# clever_watch.net
KiCad netlist of a schematic drawn in Altium Designer
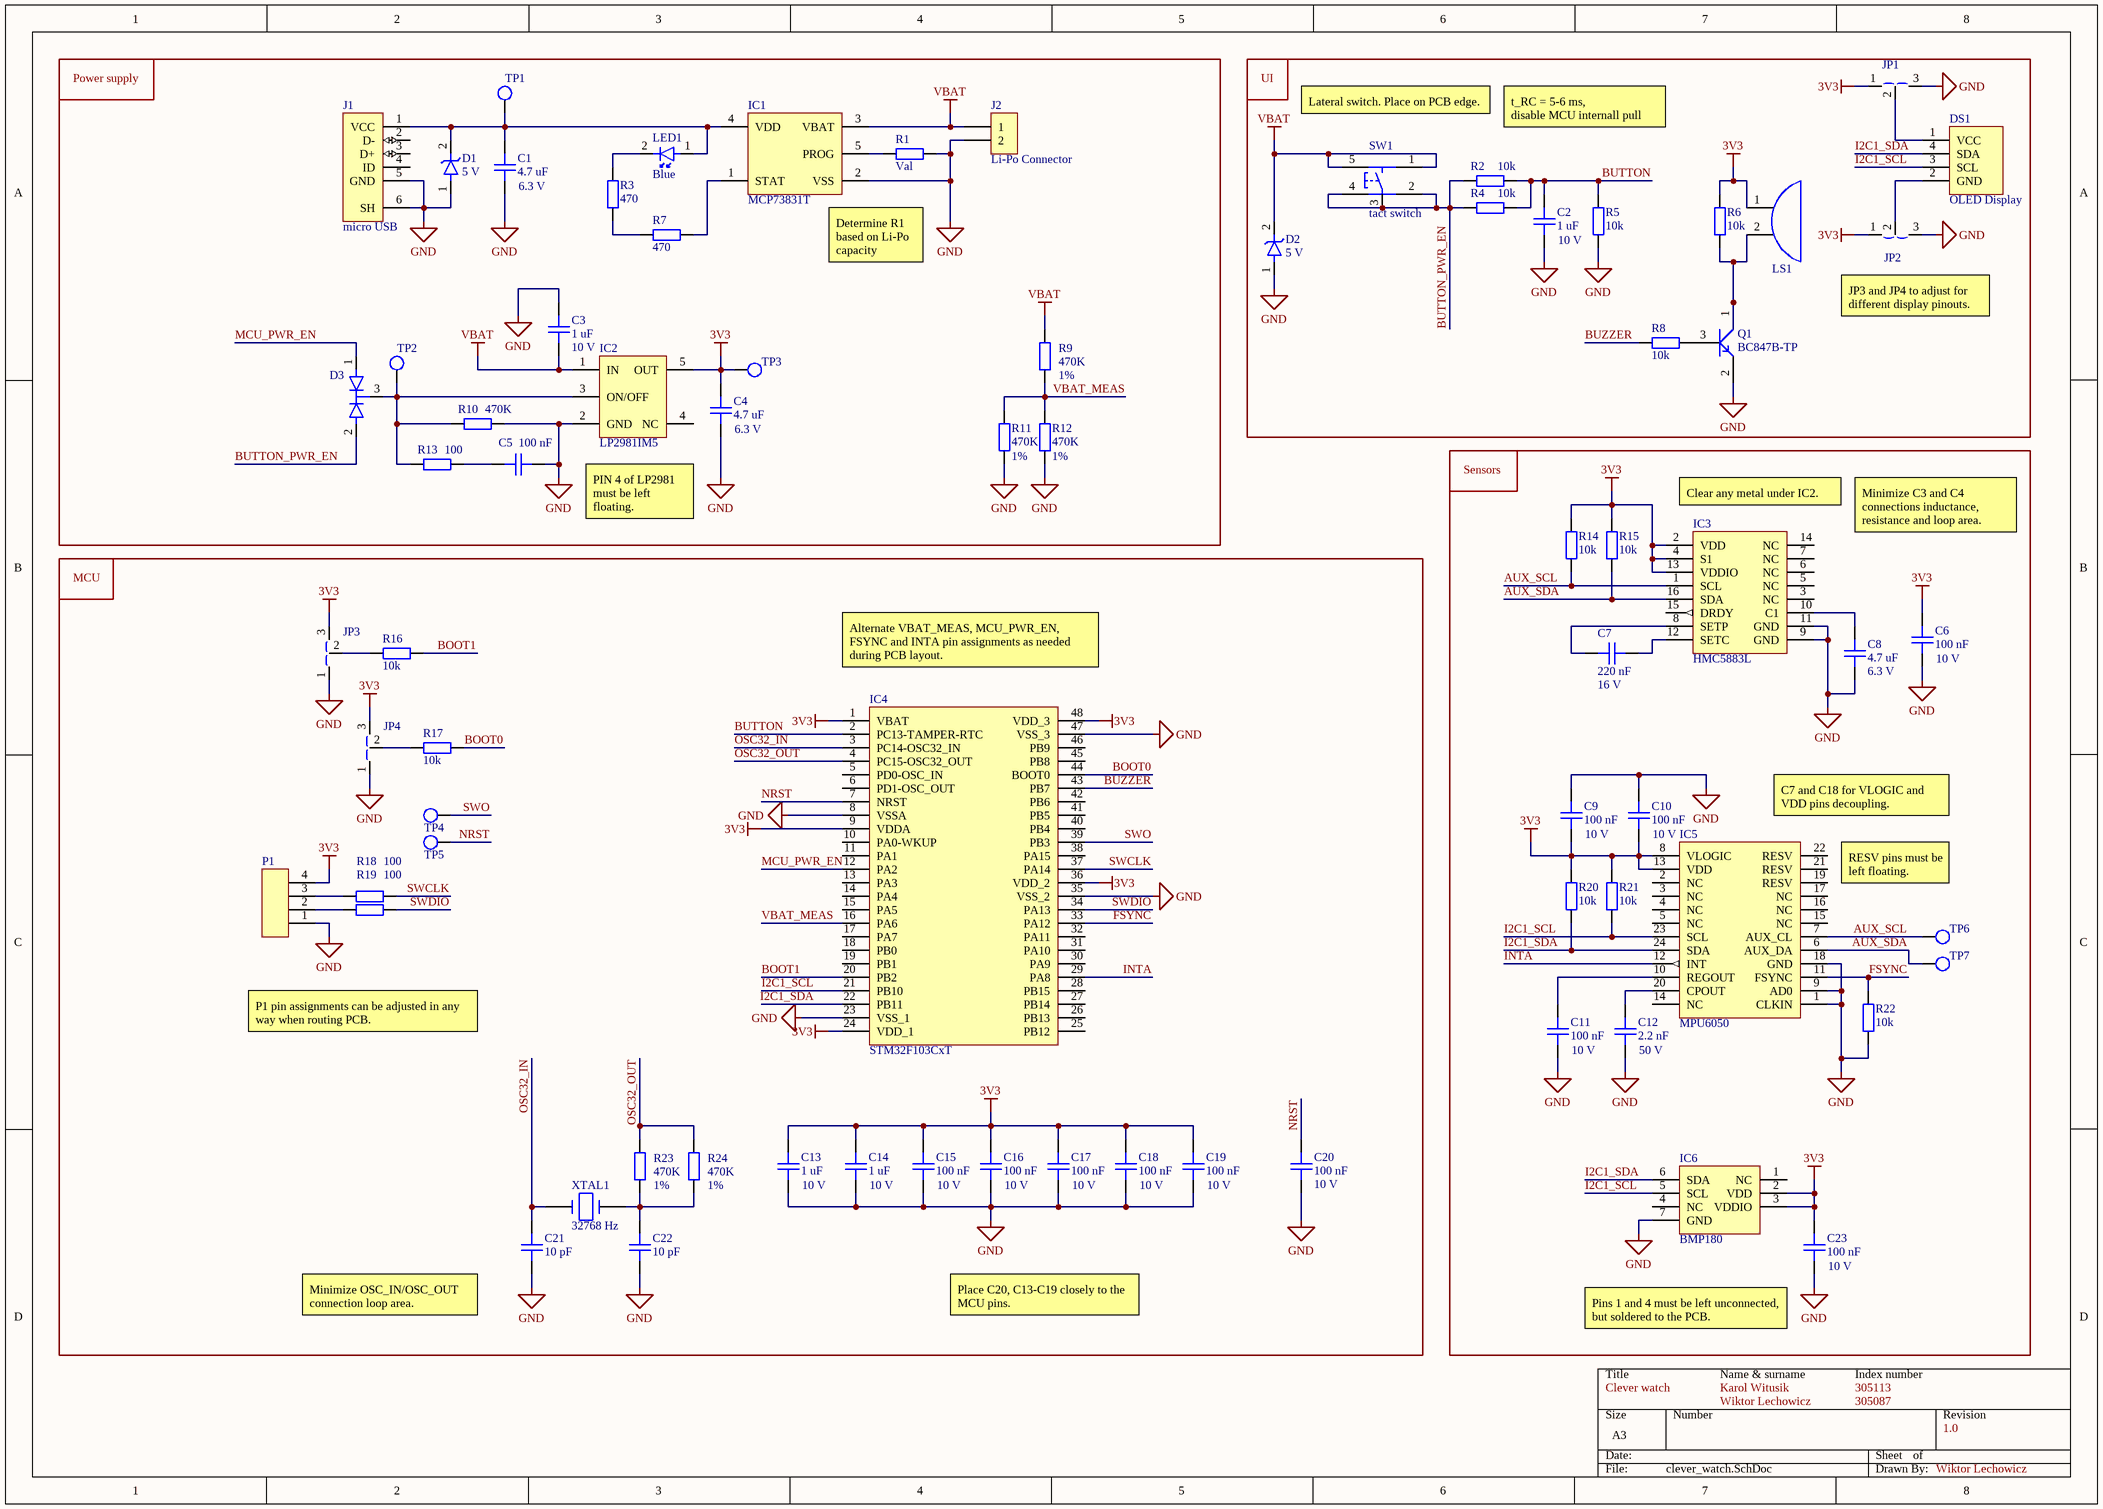
[diagram p0: clever_watch.SchDoc]

(export (version "E")
  (design (tool "Eeschema 10.0.6"))
  (components
    (comp (ref "C1")
      (value "4.7 uF")
      (footprint "C0402")
      (fields (field (name "MPN") "GRM155R60J475ME87D") (field (name "RATED VOLTAGE") "6.3 V"))
      (libsource (lib "clever_watch") (part "C"))
    )
    (comp (ref "C2")
      (value "1 uF")
      (footprint "C0402")
      (fields (field (name "MPN") "GRM155R61A105KE15J") (field (name "RATED VOLTAGE") "10 V"))
      (libsource (lib "clever_watch") (part "C"))
    )
    (comp (ref "C3")
      (value "1 uF")
      (footprint "C0402")
      (fields (field (name "MPN") "GRM155R61A105KE15J") (field (name "RATED VOLTAGE") "10 V"))
      (libsource (lib "clever_watch") (part "C"))
    )
    (comp (ref "C4")
      (value "4.7 uF")
      (footprint "C0402")
      (fields (field (name "MPN") "GRM155R60J475ME87D") (field (name "RATED VOLTAGE") "6.3 V"))
      (libsource (lib "clever_watch") (part "C"))
    )
    (comp (ref "C5")
      (value "100 nF")
      (footprint "C0402")
      (fields (field (name "MPN") "CL05A104KP5NNNC"))
      (libsource (lib "clever_watch") (part "C"))
    )
    (comp (ref "C6")
      (value "100 nF")
      (footprint "C0402")
      (fields (field (name "MPN") "CL05A104KP5NNNC") (field (name "RATED VOLTAGE") "10 V"))
      (libsource (lib "clever_watch") (part "C"))
    )
    (comp (ref "C7")
      (value "220 nF")
      (footprint "C0402")
      (fields (field (name "MPN") "CL05B224KO5NNNC") (field (name "RATED VOLTAGE") "16 V"))
      (libsource (lib "clever_watch") (part "C"))
    )
    (comp (ref "C8")
      (value "4.7 uF")
      (footprint "C0603")
      (fields (field (name "MPN") "GRM155R60J475ME87D") (field (name "RATED VOLTAGE") "6.3 V"))
      (libsource (lib "clever_watch") (part "C"))
    )
    (comp (ref "C9")
      (value "100 nF")
      (footprint "C0402")
      (fields (field (name "MPN") "CL05A104KP5NNNC") (field (name "RATED VOLTAGE") "10 V"))
      (libsource (lib "clever_watch") (part "C"))
    )
    (comp (ref "C10")
      (value "100 nF")
      (footprint "C0402")
      (fields (field (name "MPN") "CL05A104KP5NNNC") (field (name "RATED VOLTAGE") "10 V"))
      (libsource (lib "clever_watch") (part "C"))
    )
    (comp (ref "C11")
      (value "100 nF")
      (footprint "C0402")
      (fields (field (name "MPN") "CL05A104KP5NNNC") (field (name "RATED VOLTAGE") "10 V"))
      (libsource (lib "clever_watch") (part "C"))
    )
    (comp (ref "C12")
      (value "2.2 nF")
      (footprint "C0402")
      (fields (field (name "MPN") "CC0402KRX7R9BB222") (field (name "RATED VOLTAGE") "50 V"))
      (libsource (lib "clever_watch") (part "C"))
    )
    (comp (ref "C13")
      (value "1 uF")
      (footprint "C0402")
      (fields (field (name "MPN") "GRM155R61A105KE15J") (field (name "RATED VOLTAGE") "10 V"))
      (libsource (lib "clever_watch") (part "C"))
    )
    (comp (ref "C14")
      (value "1 uF")
      (footprint "C0402")
      (fields (field (name "MPN") "GRM155R61A105KE15J") (field (name "RATED VOLTAGE") "10 V"))
      (libsource (lib "clever_watch") (part "C"))
    )
    (comp (ref "C15")
      (value "100 nF")
      (footprint "C0402")
      (fields (field (name "MPN") "CL05A104KP5NNNC") (field (name "RATED VOLTAGE") "10 V"))
      (libsource (lib "clever_watch") (part "C"))
    )
    (comp (ref "C16")
      (value "100 nF")
      (footprint "C0402")
      (fields (field (name "MPN") "CL05A104KP5NNNC") (field (name "RATED VOLTAGE") "10 V"))
      (libsource (lib "clever_watch") (part "C"))
    )
    (comp (ref "C17")
      (value "100 nF")
      (footprint "C0402")
      (fields (field (name "MPN") "CL05A104KP5NNNC") (field (name "RATED VOLTAGE") "10 V"))
      (libsource (lib "clever_watch") (part "C"))
    )
    (comp (ref "C18")
      (value "100 nF")
      (footprint "C0402")
      (fields (field (name "MPN") "CL05A104KP5NNNC") (field (name "RATED VOLTAGE") "10 V"))
      (libsource (lib "clever_watch") (part "C"))
    )
    (comp (ref "C19")
      (value "100 nF")
      (footprint "C0402")
      (fields (field (name "MPN") "CL05A104KP5NNNC") (field (name "RATED VOLTAGE") "10 V"))
      (libsource (lib "clever_watch") (part "C"))
    )
    (comp (ref "C20")
      (value "100 nF")
      (footprint "C0402")
      (fields (field (name "MPN") "CL05A104KP5NNNC") (field (name "RATED VOLTAGE") "10 V"))
      (libsource (lib "clever_watch") (part "C"))
    )
    (comp (ref "C21")
      (value "10 pF")
      (footprint "C0402")
      (fields (field (name "MPN") "CC0402JRNPO9BN100"))
      (libsource (lib "clever_watch") (part "C"))
    )
    (comp (ref "C22")
      (value "10 pF")
      (footprint "C0402")
      (fields (field (name "MPN") "CC0402JRNPO9BN100"))
      (libsource (lib "clever_watch") (part "C"))
    )
    (comp (ref "C23")
      (value "100 nF")
      (footprint "C0402")
      (fields (field (name "MPN") "CL05A104KP5NNNC") (field (name "RATED VOLTAGE") "10 V"))
      (libsource (lib "clever_watch") (part "C"))
    )
    (comp (ref "D1")
      (value "5 V")
      (footprint "SOD-323FL_477AB_ONS")
      (fields (field (name "MPN") "ESD3Z5V0"))
      (libsource (lib "clever_watch") (part "TVS_DIODE"))
    )
    (comp (ref "D2")
      (value "5 V")
      (footprint "SOD-323FL_477AB_ONS")
      (fields (field (name "MPN") "ESD3Z5V0"))
      (libsource (lib "clever_watch") (part "TVS_DIODE"))
    )
    (comp (ref "D3")
      (value "D_DOUBLE_CK2")
      (footprint "SOT65P210X110-3N")
      (fields (field (name "MPN") "1PS70SB85.115"))
      (libsource (lib "clever_watch") (part "D_DOUBLE_CK2"))
    )
    (comp (ref "DS1")
      (value "OLED Display")
      (footprint "OLED SSD1306")
      (fields (field (name "MPN") "OLED-SSD1306"))
      (libsource (lib "clever_watch") (part "OLED"))
    )
    (comp (ref "IC1")
      (value "MCP73831T")
      (footprint "SOT-23-5_MC_MCH")
      (fields (field (name "MPN") "MCP73831T-2ACI/OT"))
      (libsource (lib "clever_watch") (part "MCP73831T-xxxx/OT"))
    )
    (comp (ref "IC2")
      (value "LP2981IM5")
      (footprint "SOT-23-5_MC_MCH")
      (fields (field (name "MPN") "LP2981IM5-3.3/NOPB"))
      (libsource (lib "clever_watch") (part "LP2981IM5"))
    )
    (comp (ref "IC3")
      (value "HMC5883L")
      (footprint "LPCC16_HNW")
      (libsource (lib "clever_watch") (part "HMC5883L"))
    )
    (comp (ref "IC4")
      (value "STM32F103CxT")
      (footprint "LQFP48-7x7mm")
      (fields (field (name "MPN") "STM32F103C8T6"))
      (libsource (lib "clever_watch") (part "STM32F103CxT"))
    )
    (comp (ref "IC5")
      (value "MPU6050")
      (footprint "QFN24_4X4X0P9_IVS")
      (libsource (lib "clever_watch") (part "MPU6050"))
    )
    (comp (ref "IC6") (value "BMP180") (footprint "BMP180") (libsource (lib "clever_watch") (part "BMP180")))
    (comp (ref "J1")
      (value "micro USB")
      (footprint "AMPHENOL_10118194-0001LF")
      (fields (field (name "MPN") "10118194-0001LF"))
      (libsource (lib "clever_watch") (part "USB_MICRO"))
    )
    (comp (ref "J2")
      (value "Li-Po Connector")
      (footprint "battery connector")
      (libsource (lib "clever_watch") (part "1x2_CONNECTOR"))
    )
    (comp (ref "JP1")
      (value "JUMPER_3_PADS")
      (footprint "0402 jumper x3")
      (libsource (lib "clever_watch") (part "JUMPER_3_PADS"))
    )
    (comp (ref "JP2")
      (value "JUMPER_3_PADS")
      (footprint "0402 jumper x3")
      (libsource (lib "") (part "JUMPER_3_PADS_1"))
    )
    (comp (ref "JP3")
      (value "JUMPER_3_PADS")
      (footprint "0402 jumper x3")
      (libsource (lib "clever_watch") (part "JUMPER_3_PADS"))
    )
    (comp (ref "JP4")
      (value "JUMPER_3_PADS")
      (footprint "0402 jumper x3")
      (libsource (lib "clever_watch") (part "JUMPER_3_PADS"))
    )
    (comp (ref "LED1")
      (value "Blue")
      (footprint "LED_0603")
      (fields (field (name "MPN") "RF-BUB190TS-CA"))
      (libsource (lib "clever_watch") (part "LED"))
    )
    (comp (ref "LS1")
      (value "BUZZER")
      (footprint "HDR_1X2_MALE")
      (fields (field (name "MPN") "LD-EDPE-1209"))
      (libsource (lib "clever_watch") (part "BUZZER"))
    )
    (comp (ref "P1")
      (value "1x4 Header")
      (footprint "CONN_15-91-2045_MOL")
      (fields (field (name "MPN") "ZL315-4SGH"))
      (libsource (lib "clever_watch") (part "1x4_HEADER"))
    )
    (comp (ref "Q1")
      (value "Q_NPN_BEC")
      (footprint "SOT-23")
      (fields (field (name "MPN") "BC847B-TP"))
      (libsource (lib "clever_watch") (part "Q_NPN_BEC"))
    )
    (comp (ref "R1") (value "Val") (footprint "R0402") (libsource (lib "clever_watch") (part "R")))
    (comp (ref "R2")
      (value "10k")
      (footprint "R0402")
      (fields (field (name "MPN") "RC0402FR-0710KL") (field (name "TOLERANCE") "1%"))
      (libsource (lib "clever_watch") (part "R"))
    )
    (comp (ref "R3")
      (value "470")
      (footprint "R0402")
      (fields (field (name "MPN") "RC0402FR-07470R"))
      (libsource (lib "clever_watch") (part "R"))
    )
    (comp (ref "R4")
      (value "10k")
      (footprint "R0402")
      (fields (field (name "MPN") "RC0402FR-0710KL") (field (name "TOLERANCE") "1%"))
      (libsource (lib "clever_watch") (part "R"))
    )
    (comp (ref "R5")
      (value "10k")
      (footprint "R0402")
      (fields (field (name "MPN") "RC0402FR-0710KL") (field (name "TOLERANCE") "1%"))
      (libsource (lib "clever_watch") (part "R"))
    )
    (comp (ref "R6")
      (value "10k")
      (footprint "R0402")
      (fields (field (name "MPN") "RC0402FR-0710KL") (field (name "TOLERANCE") "1%"))
      (libsource (lib "clever_watch") (part "R"))
    )
    (comp (ref "R7")
      (value "470")
      (footprint "R0402")
      (fields (field (name "MPN") "RC0402FR-07470R"))
      (libsource (lib "clever_watch") (part "R"))
    )
    (comp (ref "R8")
      (value "10k")
      (footprint "R0402")
      (fields (field (name "MPN") "RC0402FR-0710KL") (field (name "TOLERANCE") "1%"))
      (libsource (lib "clever_watch") (part "R"))
    )
    (comp (ref "R9")
      (value "470K")
      (footprint "R0402")
      (fields (field (name "MPN") "AC0402FR-07470KL") (field (name "TOLERANCE") "1%"))
      (libsource (lib "clever_watch") (part "R"))
    )
    (comp (ref "R10")
      (value "470K")
      (footprint "R0402")
      (fields (field (name "MPN") "AC0402FR-07470KL") (field (name "TOLERANCE") "1%"))
      (libsource (lib "clever_watch") (part "R"))
    )
    (comp (ref "R11")
      (value "470K")
      (footprint "R0402")
      (fields (field (name "MPN") "AC0402FR-07470KL") (field (name "TOLERANCE") "1%"))
      (libsource (lib "clever_watch") (part "R"))
    )
    (comp (ref "R12")
      (value "470K")
      (footprint "R0402")
      (fields (field (name "MPN") "AC0402FR-07470KL") (field (name "TOLERANCE") "1%"))
      (libsource (lib "clever_watch") (part "R"))
    )
    (comp (ref "R13") (value "100") (footprint "R0402") (libsource (lib "clever_watch") (part "R")))
    (comp (ref "R14")
      (value "10k")
      (footprint "R0402")
      (fields (field (name "MPN") "RC0402FR-0710KL") (field (name "TOLERANCE") "1%"))
      (libsource (lib "clever_watch") (part "R"))
    )
    (comp (ref "R15")
      (value "10k")
      (footprint "R0402")
      (fields (field (name "MPN") "RC0402FR-0710KL") (field (name "TOLERANCE") "1%"))
      (libsource (lib "clever_watch") (part "R"))
    )
    (comp (ref "R16")
      (value "10k")
      (footprint "R0402")
      (fields (field (name "MPN") "RC0402FR-0710KL") (field (name "TOLERANCE") "1%"))
      (libsource (lib "clever_watch") (part "R"))
    )
    (comp (ref "R17")
      (value "10k")
      (footprint "R0402")
      (fields (field (name "MPN") "RC0402FR-0710KL") (field (name "TOLERANCE") "1%"))
      (libsource (lib "clever_watch") (part "R"))
    )
    (comp (ref "R18")
      (value "100")
      (footprint "R0402")
      (fields (field (name "MPN") "RC0402FR-07100RL") (field (name "TOLERANCE") "1%"))
      (libsource (lib "clever_watch") (part "R"))
    )
    (comp (ref "R19")
      (value "100")
      (footprint "R0402")
      (fields (field (name "MPN") "RC0402FR-07100RL") (field (name "TOLERANCE") "1%"))
      (libsource (lib "clever_watch") (part "R"))
    )
    (comp (ref "R20")
      (value "10k")
      (footprint "R0402")
      (fields (field (name "MPN") "RC0402FR-0710KL") (field (name "TOLERANCE") "1%"))
      (libsource (lib "clever_watch") (part "R"))
    )
    (comp (ref "R21")
      (value "10k")
      (footprint "R0402")
      (fields (field (name "MPN") "RC0402FR-0710KL") (field (name "TOLERANCE") "1%"))
      (libsource (lib "clever_watch") (part "R"))
    )
    (comp (ref "R22")
      (value "10k")
      (footprint "R0402")
      (fields (field (name "MPN") "RC0402FR-0710KL") (field (name "TOLERANCE") "1%"))
      (libsource (lib "clever_watch") (part "R"))
    )
    (comp (ref "R23")
      (value "470K")
      (footprint "R0402")
      (fields (field (name "MPN") "AC0402FR-07470KL") (field (name "TOLERANCE") "1%"))
      (libsource (lib "clever_watch") (part "R"))
    )
    (comp (ref "R24")
      (value "470K")
      (footprint "R0402")
      (fields (field (name "MPN") "AC0402FR-07470KL") (field (name "TOLERANCE") "1%"))
      (libsource (lib "clever_watch") (part "R"))
    )
    (comp (ref "SW1")
      (value "tact switch")
      (footprint "KMS221GLFS")
      (fields (field (name "MPN") "KMS221G LFS"))
      (libsource (lib "clever_watch") (part "TACT-SW"))
    )
    (comp (ref "TP1")
      (value "TEST_POINT")
      (footprint "Testpoint")
      (libsource (lib "clever_watch") (part "TEST_POINT"))
    )
    (comp (ref "TP2")
      (value "TEST_POINT")
      (footprint "Testpoint")
      (libsource (lib "clever_watch") (part "TEST_POINT"))
    )
    (comp (ref "TP3")
      (value "TEST_POINT")
      (footprint "Testpoint")
      (libsource (lib "clever_watch") (part "TEST_POINT"))
    )
    (comp (ref "TP4")
      (value "TEST_POINT")
      (footprint "Testpoint")
      (libsource (lib "clever_watch") (part "TEST_POINT"))
    )
    (comp (ref "TP5")
      (value "TEST_POINT")
      (footprint "Testpoint")
      (libsource (lib "clever_watch") (part "TEST_POINT"))
    )
    (comp (ref "TP6")
      (value "TEST_POINT")
      (footprint "Testpoint")
      (libsource (lib "clever_watch") (part "TEST_POINT"))
    )
    (comp (ref "TP7")
      (value "TEST_POINT")
      (footprint "Testpoint")
      (libsource (lib "clever_watch") (part "TEST_POINT"))
    )
    (comp (ref "XTAL1")
      (value "32768 Hz")
      (footprint "ABS0732768KHZ7T")
      (fields (field (name "MPN") "ABS07-32.768KHZ-7-T"))
      (libsource (lib "clever_watch") (part "CRYSTAL_OSC_2PINS"))
    )
  )
  (nets
    (net (code "1") (name "/AUX_SCL") (class "Default")
      (node (ref "IC3") (pin "1") (pinfunction "SCL_1") (pintype "open_collector"))
      (node (ref "IC5") (pin "7") (pinfunction "AUX_CL_7") (pintype "open_collector"))
      (node (ref "R14") (pin "1") (pinfunction "1_1") (pintype "passive"))
      (node (ref "TP6") (pin "1") (pinfunction "1_1") (pintype "passive"))
    )
    (net (code "2") (name "/AUX_SDA") (class "Default")
      (node (ref "IC3") (pin "16") (pinfunction "SDA_16") (pintype "open_collector"))
      (node (ref "IC5") (pin "6") (pinfunction "AUX_DA_6") (pintype "open_collector"))
      (node (ref "R15") (pin "1") (pinfunction "1_1") (pintype "passive"))
      (node (ref "TP7") (pin "1") (pinfunction "1_1") (pintype "passive"))
    )
    (net (code "3") (name "/BOOT0") (class "Default")
      (node (ref "IC4") (pin "44") (pinfunction "BOOT0_44") (pintype "passive"))
      (node (ref "R17") (pin "2") (pinfunction "2_2") (pintype "passive"))
    )
    (net (code "4") (name "/BOOT1") (class "Default")
      (node (ref "IC4") (pin "20") (pinfunction "PB2_20") (pintype "passive"))
      (node (ref "R16") (pin "2") (pinfunction "2_2") (pintype "passive"))
    )
    (net (code "5") (name "/BUTTON") (class "Default")
      (node (ref "C2") (pin "2") (pinfunction "2_2") (pintype "passive"))
      (node (ref "IC4") (pin "2") (pinfunction "PC13-TAMPER-RTC_2") (pintype "passive"))
      (node (ref "R2") (pin "1") (pinfunction "1_1") (pintype "passive"))
      (node (ref "R4") (pin "1") (pinfunction "1_1") (pintype "passive"))
      (node (ref "R5") (pin "1") (pinfunction "1_1") (pintype "passive"))
    )
    (net (code "6") (name "/BUTTON_PWR_EN") (class "Default")
      (node (ref "D3") (pin "2") (pinfunction "A2_2") (pintype "passive"))
      (node (ref "R2") (pin "2") (pinfunction "2_2") (pintype "passive"))
      (node (ref "R4") (pin "2") (pinfunction "2_2") (pintype "passive"))
      (node (ref "SW1") (pin "2") (pinfunction "2_2") (pintype "passive"))
      (node (ref "SW1") (pin "3") (pinfunction "3_3") (pintype "passive"))
      (node (ref "SW1") (pin "4") (pinfunction "4_4") (pintype "passive"))
    )
    (net (code "7") (name "/BUZZER") (class "Default")
      (node (ref "IC4") (pin "43") (pinfunction "PB7_43") (pintype "passive"))
      (node (ref "R8") (pin "1") (pinfunction "1_1") (pintype "passive"))
    )
    (net (code "8") (name "/FSYNC") (class "Default")
      (node (ref "IC4") (pin "33") (pinfunction "PA12_33") (pintype "passive"))
      (node (ref "IC5") (pin "11") (pinfunction "FSYNC_11") (pintype "passive"))
      (node (ref "R22") (pin "2") (pinfunction "2_2") (pintype "passive"))
    )
    (net (code "9") (name "/I2C1_SCL") (class "Default")
      (node (ref "DS1") (pin "3") (pinfunction "SCL_3") (pintype "open_collector"))
      (node (ref "IC4") (pin "21") (pinfunction "PB10_21") (pintype "passive"))
      (node (ref "IC5") (pin "23") (pinfunction "SCL_23") (pintype "open_collector"))
      (node (ref "IC6") (pin "5") (pinfunction "SCL_5") (pintype "open_collector"))
      (node (ref "R21") (pin "1") (pinfunction "1_1") (pintype "passive"))
    )
    (net (code "10") (name "/I2C1_SDA") (class "Default")
      (node (ref "DS1") (pin "4") (pinfunction "SDA_4") (pintype "open_collector"))
      (node (ref "IC4") (pin "22") (pinfunction "PB11_22") (pintype "passive"))
      (node (ref "IC5") (pin "24") (pinfunction "SDA_24") (pintype "open_collector"))
      (node (ref "IC6") (pin "6") (pinfunction "SDA_6") (pintype "open_collector"))
      (node (ref "R20") (pin "1") (pinfunction "1_1") (pintype "passive"))
    )
    (net (code "11") (name "/INTA") (class "Default")
      (node (ref "IC4") (pin "29") (pinfunction "PA8_29") (pintype "passive"))
      (node (ref "IC5") (pin "12") (pinfunction "INT_12") (pintype "output"))
    )
    (net (code "12") (name "/MCU_PWR_EN") (class "Default")
      (node (ref "D3") (pin "1") (pinfunction "A1_1") (pintype "passive"))
      (node (ref "IC4") (pin "12") (pinfunction "PA2_12") (pintype "passive"))
    )
    (net (code "13") (name "/NRST") (class "Default")
      (node (ref "C20") (pin "2") (pinfunction "2_2") (pintype "passive"))
      (node (ref "IC4") (pin "7") (pinfunction "NRST_7") (pintype "passive"))
      (node (ref "TP5") (pin "1") (pinfunction "1_1") (pintype "passive"))
    )
    (net (code "14") (name "/OSC32_IN") (class "Default")
      (node (ref "C21") (pin "1") (pinfunction "1_1") (pintype "passive"))
      (node (ref "IC4") (pin "3") (pinfunction "PC14-OSC32_IN_3") (pintype "passive"))
      (node (ref "XTAL1") (pin "1") (pinfunction "1_1") (pintype "passive"))
    )
    (net (code "15") (name "/OSC32_OUT") (class "Default")
      (node (ref "IC4") (pin "4") (pinfunction "PC15-OSC32_OUT_4") (pintype "passive"))
      (node (ref "R23") (pin "1") (pinfunction "1_1") (pintype "passive"))
      (node (ref "R24") (pin "1") (pinfunction "1_1") (pintype "passive"))
    )
    (net (code "16") (name "/SWCLK") (class "Default")
      (node (ref "IC4") (pin "37") (pinfunction "PA14_37") (pintype "passive"))
      (node (ref "R18") (pin "2") (pinfunction "2_2") (pintype "passive"))
    )
    (net (code "17") (name "/SWDIO") (class "Default")
      (node (ref "IC4") (pin "34") (pinfunction "PA13_34") (pintype "passive"))
      (node (ref "R19") (pin "2") (pinfunction "2_2") (pintype "passive"))
    )
    (net (code "18") (name "/SWO") (class "Default")
      (node (ref "IC4") (pin "39") (pinfunction "PB3_39") (pintype "passive"))
      (node (ref "TP4") (pin "1") (pinfunction "1_1") (pintype "passive"))
    )
    (net (code "19") (name "/VBAT_MEAS") (class "Default")
      (node (ref "IC4") (pin "16") (pinfunction "PA6_16") (pintype "passive"))
      (node (ref "R11") (pin "2") (pinfunction "2_2") (pintype "passive"))
      (node (ref "R12") (pin "2") (pinfunction "2_2") (pintype "passive"))
      (node (ref "R9") (pin "2") (pinfunction "2_2") (pintype "passive"))
    )
    (net (code "20") (name "3V3") (class "Default")
      (node (ref "C10") (pin "1") (pinfunction "1_1") (pintype "passive"))
      (node (ref "C13") (pin "2") (pinfunction "2_2") (pintype "passive"))
      (node (ref "C14") (pin "2") (pinfunction "2_2") (pintype "passive"))
      (node (ref "C15") (pin "2") (pinfunction "2_2") (pintype "passive"))
      (node (ref "C16") (pin "2") (pinfunction "2_2") (pintype "passive"))
      (node (ref "C17") (pin "2") (pinfunction "2_2") (pintype "passive"))
      (node (ref "C18") (pin "2") (pinfunction "2_2") (pintype "passive"))
      (node (ref "C19") (pin "2") (pinfunction "2_2") (pintype "passive"))
      (node (ref "C23") (pin "2") (pinfunction "2_2") (pintype "passive"))
      (node (ref "C4") (pin "2") (pinfunction "2_2") (pintype "passive"))
      (node (ref "C6") (pin "2") (pinfunction "2_2") (pintype "passive"))
      (node (ref "C9") (pin "1") (pinfunction "1_1") (pintype "passive"))
      (node (ref "IC2") (pin "5") (pinfunction "OUT_5") (pintype "power_in"))
      (node (ref "IC3") (pin "13") (pinfunction "VDDIO_13") (pintype "power_in"))
      (node (ref "IC3") (pin "2") (pinfunction "VDD_2") (pintype "power_in"))
      (node (ref "IC3") (pin "4") (pinfunction "S1_4") (pintype "passive"))
      (node (ref "IC4") (pin "1") (pinfunction "VBAT_1") (pintype "power_in"))
      (node (ref "IC4") (pin "24") (pinfunction "VDD_1_24") (pintype "power_in"))
      (node (ref "IC4") (pin "36") (pinfunction "VDD_2_36") (pintype "power_in"))
      (node (ref "IC4") (pin "48") (pinfunction "VDD_3_48") (pintype "power_in"))
      (node (ref "IC4") (pin "9") (pinfunction "VDDA_9") (pintype "power_in"))
      (node (ref "IC5") (pin "13") (pinfunction "VDD_13") (pintype "power_in"))
      (node (ref "IC5") (pin "8") (pinfunction "VLOGIC_8") (pintype "power_in"))
      (node (ref "IC6") (pin "2") (pinfunction "VDD_2") (pintype "power_in"))
      (node (ref "IC6") (pin "3") (pinfunction "VDDIO_3") (pintype "power_in"))
      (node (ref "JP1") (pin "1") (pinfunction "1_1") (pintype "passive"))
      (node (ref "JP2") (pin "1") (pinfunction "1_1") (pintype "passive"))
      (node (ref "JP3") (pin "3") (pinfunction "3_3") (pintype "passive"))
      (node (ref "JP4") (pin "3") (pinfunction "3_3") (pintype "passive"))
      (node (ref "LS1") (pin "1") (pinfunction "1_1") (pintype "passive"))
      (node (ref "P1") (pin "4") (pinfunction "4_4") (pintype "passive"))
      (node (ref "R14") (pin "2") (pinfunction "2_2") (pintype "passive"))
      (node (ref "R15") (pin "2") (pinfunction "2_2") (pintype "passive"))
      (node (ref "R20") (pin "2") (pinfunction "2_2") (pintype "passive"))
      (node (ref "R21") (pin "2") (pinfunction "2_2") (pintype "passive"))
      (node (ref "R6") (pin "2") (pinfunction "2_2") (pintype "passive"))
      (node (ref "TP3") (pin "1") (pinfunction "1_1") (pintype "passive"))
    )
    (net (code "21") (name "GND") (class "Default")
      (node (ref "C1") (pin "1") (pinfunction "1_1") (pintype "passive"))
      (node (ref "C10") (pin "2") (pinfunction "2_2") (pintype "passive"))
      (node (ref "C11") (pin "1") (pinfunction "1_1") (pintype "passive"))
      (node (ref "C12") (pin "1") (pinfunction "1_1") (pintype "passive"))
      (node (ref "C13") (pin "1") (pinfunction "1_1") (pintype "passive"))
      (node (ref "C14") (pin "1") (pinfunction "1_1") (pintype "passive"))
      (node (ref "C15") (pin "1") (pinfunction "1_1") (pintype "passive"))
      (node (ref "C16") (pin "1") (pinfunction "1_1") (pintype "passive"))
      (node (ref "C17") (pin "1") (pinfunction "1_1") (pintype "passive"))
      (node (ref "C18") (pin "1") (pinfunction "1_1") (pintype "passive"))
      (node (ref "C19") (pin "1") (pinfunction "1_1") (pintype "passive"))
      (node (ref "C2") (pin "1") (pinfunction "1_1") (pintype "passive"))
      (node (ref "C20") (pin "1") (pinfunction "1_1") (pintype "passive"))
      (node (ref "C21") (pin "2") (pinfunction "2_2") (pintype "passive"))
      (node (ref "C22") (pin "2") (pinfunction "2_2") (pintype "passive"))
      (node (ref "C23") (pin "1") (pinfunction "1_1") (pintype "passive"))
      (node (ref "C3") (pin "1") (pinfunction "1_1") (pintype "passive"))
      (node (ref "C4") (pin "1") (pinfunction "1_1") (pintype "passive"))
      (node (ref "C5") (pin "1") (pinfunction "1_1") (pintype "passive"))
      (node (ref "C6") (pin "1") (pinfunction "1_1") (pintype "passive"))
      (node (ref "C8") (pin "1") (pinfunction "1_1") (pintype "passive"))
      (node (ref "C9") (pin "2") (pinfunction "2_2") (pintype "passive"))
      (node (ref "D1") (pin "1") (pinfunction "A_1") (pintype "passive"))
      (node (ref "D2") (pin "1") (pinfunction "A_1") (pintype "passive"))
      (node (ref "IC1") (pin "2") (pinfunction "VSS_2") (pintype "power_in"))
      (node (ref "IC2") (pin "2") (pinfunction "GND_2") (pintype "power_in"))
      (node (ref "IC3") (pin "11") (pinfunction "GND_11") (pintype "power_in"))
      (node (ref "IC3") (pin "9") (pinfunction "GND_9") (pintype "power_in"))
      (node (ref "IC4") (pin "23") (pinfunction "VSS_1_23") (pintype "power_in"))
      (node (ref "IC4") (pin "35") (pinfunction "VSS_2_35") (pintype "power_in"))
      (node (ref "IC4") (pin "47") (pinfunction "VSS_3_47") (pintype "power_in"))
      (node (ref "IC4") (pin "8") (pinfunction "VSSA_8") (pintype "power_in"))
      (node (ref "IC5") (pin "1") (pinfunction "CLKIN_1") (pintype "passive"))
      (node (ref "IC5") (pin "18") (pinfunction "GND_18") (pintype "power_in"))
      (node (ref "IC5") (pin "9") (pinfunction "AD0_9") (pintype "passive"))
      (node (ref "IC6") (pin "7") (pinfunction "GND_7") (pintype "power_in"))
      (node (ref "J1") (pin "5") (pinfunction "GND_5") (pintype "power_in"))
      (node (ref "J1") (pin "6") (pinfunction "SH_6") (pintype "power_in"))
      (node (ref "J2") (pin "2") (pinfunction "2_2") (pintype "passive"))
      (node (ref "JP1") (pin "3") (pinfunction "3_3") (pintype "passive"))
      (node (ref "JP2") (pin "3") (pinfunction "3_3") (pintype "passive"))
      (node (ref "JP3") (pin "1") (pinfunction "1_1") (pintype "passive"))
      (node (ref "JP4") (pin "1") (pinfunction "1_1") (pintype "passive"))
      (node (ref "P1") (pin "1") (pinfunction "1_1") (pintype "passive"))
      (node (ref "Q1") (pin "2") (pinfunction "E_2") (pintype "passive"))
      (node (ref "R1") (pin "1") (pinfunction "1_1") (pintype "passive"))
      (node (ref "R10") (pin "2") (pinfunction "2_2") (pintype "passive"))
      (node (ref "R11") (pin "1") (pinfunction "1_1") (pintype "passive"))
      (node (ref "R12") (pin "1") (pinfunction "1_1") (pintype "passive"))
      (node (ref "R22") (pin "1") (pinfunction "1_1") (pintype "passive"))
      (node (ref "R5") (pin "2") (pinfunction "2_2") (pintype "passive"))
    )
    (net (code "22") (name "Net-(C5-Pad2)") (class "Default")
      (node (ref "C5") (pin "2") (pinfunction "2_2") (pintype "passive"))
      (node (ref "R13") (pin "2") (pinfunction "2_2") (pintype "passive"))
    )
    (net (code "23") (name "Net-(C22-Pad1)") (class "Default")
      (node (ref "C22") (pin "1") (pinfunction "1_1") (pintype "passive"))
      (node (ref "R23") (pin "2") (pinfunction "2_2") (pintype "passive"))
      (node (ref "R24") (pin "2") (pinfunction "2_2") (pintype "passive"))
      (node (ref "XTAL1") (pin "2") (pinfunction "2_2") (pintype "passive"))
    )
    (net (code "24") (name "Net-(D1-K)") (class "Default")
      (node (ref "C1") (pin "2") (pinfunction "2_2") (pintype "passive"))
      (node (ref "D1") (pin "2") (pinfunction "K_2") (pintype "passive"))
      (node (ref "IC1") (pin "4") (pinfunction "VDD_4") (pintype "power_in"))
      (node (ref "J1") (pin "1") (pinfunction "VCC_1") (pintype "power_in"))
      (node (ref "LED1") (pin "1") (pinfunction "Anode_1") (pintype "passive"))
      (node (ref "TP1") (pin "1") (pinfunction "1_1") (pintype "passive"))
    )
    (net (code "25") (name "Net-(D3-K)") (class "Default")
      (node (ref "D3") (pin "3") (pinfunction "K_3") (pintype "passive"))
      (node (ref "IC2") (pin "3") (pinfunction "ON/OFF_3") (pintype "passive"))
      (node (ref "R10") (pin "1") (pinfunction "1_1") (pintype "passive"))
      (node (ref "R13") (pin "1") (pinfunction "1_1") (pintype "passive"))
      (node (ref "TP2") (pin "1") (pinfunction "1_1") (pintype "passive"))
    )
    (net (code "26") (name "Net-(DS1-GND)") (class "Default")
      (node (ref "DS1") (pin "2") (pinfunction "GND_2") (pintype "power_in"))
      (node (ref "JP2") (pin "2") (pinfunction "2_2") (pintype "passive"))
    )
    (net (code "27") (name "Net-(DS1-VCC)") (class "Default")
      (node (ref "DS1") (pin "1") (pinfunction "VCC_1") (pintype "power_in"))
      (node (ref "JP1") (pin "2") (pinfunction "2_2") (pintype "passive"))
    )
    (net (code "28") (name "Net-(IC1-PROG)") (class "Default")
      (node (ref "IC1") (pin "5") (pinfunction "PROG_5") (pintype "passive"))
      (node (ref "R1") (pin "2") (pinfunction "2_2") (pintype "passive"))
    )
    (net (code "29") (name "Net-(IC1-STAT)") (class "Default")
      (node (ref "IC1") (pin "1") (pinfunction "STAT_1") (pintype "passive"))
      (node (ref "R7") (pin "1") (pinfunction "1_1") (pintype "passive"))
    )
    (net (code "30") (name "Net-(IC3-C1)") (class "Default")
      (node (ref "C8") (pin "2") (pinfunction "2_2") (pintype "passive"))
      (node (ref "IC3") (pin "10") (pinfunction "C1_10") (pintype "passive"))
    )
    (net (code "31") (name "Net-(IC3-SETC)") (class "Default")
      (node (ref "C7") (pin "1") (pinfunction "1_1") (pintype "passive"))
      (node (ref "IC3") (pin "12") (pinfunction "SETC_12") (pintype "passive"))
    )
    (net (code "32") (name "Net-(IC3-SETP)") (class "Default")
      (node (ref "C7") (pin "2") (pinfunction "2_2") (pintype "passive"))
      (node (ref "IC3") (pin "8") (pinfunction "SETP_8") (pintype "passive"))
    )
    (net (code "33") (name "Net-(IC5-CPOUT)") (class "Default")
      (node (ref "C12") (pin "2") (pinfunction "2_2") (pintype "passive"))
      (node (ref "IC5") (pin "20") (pinfunction "CPOUT_20") (pintype "passive"))
    )
    (net (code "34") (name "Net-(IC5-REGOUT)") (class "Default")
      (node (ref "C11") (pin "2") (pinfunction "2_2") (pintype "passive"))
      (node (ref "IC5") (pin "10") (pinfunction "REGOUT_10") (pintype "passive"))
    )
    (net (code "35") (name "Net-(JP3-Pad2)") (class "Default")
      (node (ref "JP3") (pin "2") (pinfunction "2_2") (pintype "passive"))
      (node (ref "R16") (pin "1") (pinfunction "1_1") (pintype "passive"))
    )
    (net (code "36") (name "Net-(JP4-Pad2)") (class "Default")
      (node (ref "JP4") (pin "2") (pinfunction "2_2") (pintype "passive"))
      (node (ref "R17") (pin "1") (pinfunction "1_1") (pintype "passive"))
    )
    (net (code "37") (name "Net-(LED1-Cathode)") (class "Default")
      (node (ref "LED1") (pin "2") (pinfunction "Cathode_2") (pintype "passive"))
      (node (ref "R3") (pin "2") (pinfunction "2_2") (pintype "passive"))
    )
    (net (code "38") (name "Net-(P1-Pad2)") (class "Default")
      (node (ref "P1") (pin "2") (pinfunction "2_2") (pintype "passive"))
      (node (ref "R19") (pin "1") (pinfunction "1_1") (pintype "passive"))
    )
    (net (code "39") (name "Net-(P1-Pad3)") (class "Default")
      (node (ref "P1") (pin "3") (pinfunction "3_3") (pintype "passive"))
      (node (ref "R18") (pin "1") (pinfunction "1_1") (pintype "passive"))
    )
    (net (code "40") (name "Net-(Q1-B)") (class "Default")
      (node (ref "Q1") (pin "3") (pinfunction "B_3") (pintype "passive"))
      (node (ref "R8") (pin "2") (pinfunction "2_2") (pintype "passive"))
    )
    (net (code "41") (name "Net-(Q1-C)") (class "Default")
      (node (ref "LS1") (pin "2") (pinfunction "2_2") (pintype "passive"))
      (node (ref "Q1") (pin "1") (pinfunction "C_1") (pintype "passive"))
      (node (ref "R6") (pin "1") (pinfunction "1_1") (pintype "passive"))
    )
    (net (code "42") (name "Net-(R3-Pad1)") (class "Default")
      (node (ref "R3") (pin "1") (pinfunction "1_1") (pintype "passive"))
      (node (ref "R7") (pin "2") (pinfunction "2_2") (pintype "passive"))
    )
    (net (code "43") (name "VBAT") (class "Default")
      (node (ref "C3") (pin "2") (pinfunction "2_2") (pintype "passive"))
      (node (ref "D2") (pin "2") (pinfunction "K_2") (pintype "passive"))
      (node (ref "IC1") (pin "3") (pinfunction "VBAT_3") (pintype "power_in"))
      (node (ref "IC2") (pin "1") (pinfunction "IN_1") (pintype "power_in"))
      (node (ref "J2") (pin "1") (pinfunction "1_1") (pintype "passive"))
      (node (ref "R9") (pin "1") (pinfunction "1_1") (pintype "passive"))
      (node (ref "SW1") (pin "1") (pinfunction "1_1") (pintype "passive"))
      (node (ref "SW1") (pin "5") (pinfunction "5_5") (pintype "passive"))
    )
    (net (code "44") (name "unconnected-(IC2-NC-Pad4)") (class "Default")
      (node (ref "IC2") (pin "4") (pinfunction "NC_4") (pintype "passive"))
    )
    (net (code "45") (name "unconnected-(IC3-DRDY-Pad15)") (class "Default")
      (node (ref "IC3") (pin "15") (pinfunction "DRDY_15") (pintype "output"))
    )
    (net (code "46") (name "unconnected-(IC3-NC-Pad3)") (class "Default")
      (node (ref "IC3") (pin "3") (pinfunction "NC_3") (pintype "passive"))
    )
    (net (code "47") (name "unconnected-(IC3-NC-Pad5)") (class "Default")
      (node (ref "IC3") (pin "5") (pinfunction "NC_5") (pintype "passive"))
    )
    (net (code "48") (name "unconnected-(IC3-NC-Pad6)") (class "Default")
      (node (ref "IC3") (pin "6") (pinfunction "NC_6") (pintype "passive"))
    )
    (net (code "49") (name "unconnected-(IC3-NC-Pad7)") (class "Default")
      (node (ref "IC3") (pin "7") (pinfunction "NC_7") (pintype "passive"))
    )
    (net (code "50") (name "unconnected-(IC3-NC-Pad14)") (class "Default")
      (node (ref "IC3") (pin "14") (pinfunction "NC_14") (pintype "passive"))
    )
    (net (code "51") (name "unconnected-(IC4-PA0-WKUP-Pad10)") (class "Default")
      (node (ref "IC4") (pin "10") (pinfunction "PA0-WKUP_10") (pintype "passive"))
    )
    (net (code "52") (name "unconnected-(IC4-PA1-Pad11)") (class "Default")
      (node (ref "IC4") (pin "11") (pinfunction "PA1_11") (pintype "passive"))
    )
    (net (code "53") (name "unconnected-(IC4-PA3-Pad13)") (class "Default")
      (node (ref "IC4") (pin "13") (pinfunction "PA3_13") (pintype "passive"))
    )
    (net (code "54") (name "unconnected-(IC4-PA4-Pad14)") (class "Default")
      (node (ref "IC4") (pin "14") (pinfunction "PA4_14") (pintype "passive"))
    )
    (net (code "55") (name "unconnected-(IC4-PA5-Pad15)") (class "Default")
      (node (ref "IC4") (pin "15") (pinfunction "PA5_15") (pintype "passive"))
    )
    (net (code "56") (name "unconnected-(IC4-PA7-Pad17)") (class "Default")
      (node (ref "IC4") (pin "17") (pinfunction "PA7_17") (pintype "passive"))
    )
    (net (code "57") (name "unconnected-(IC4-PA9-Pad30)") (class "Default")
      (node (ref "IC4") (pin "30") (pinfunction "PA9_30") (pintype "passive"))
    )
    (net (code "58") (name "unconnected-(IC4-PA10-Pad31)") (class "Default")
      (node (ref "IC4") (pin "31") (pinfunction "PA10_31") (pintype "passive"))
    )
    (net (code "59") (name "unconnected-(IC4-PA11-Pad32)") (class "Default")
      (node (ref "IC4") (pin "32") (pinfunction "PA11_32") (pintype "passive"))
    )
    (net (code "60") (name "unconnected-(IC4-PA15-Pad38)") (class "Default")
      (node (ref "IC4") (pin "38") (pinfunction "PA15_38") (pintype "passive"))
    )
    (net (code "61") (name "unconnected-(IC4-PB0-Pad18)") (class "Default")
      (node (ref "IC4") (pin "18") (pinfunction "PB0_18") (pintype "passive"))
    )
    (net (code "62") (name "unconnected-(IC4-PB1-Pad19)") (class "Default")
      (node (ref "IC4") (pin "19") (pinfunction "PB1_19") (pintype "passive"))
    )
    (net (code "63") (name "unconnected-(IC4-PB4-Pad40)") (class "Default")
      (node (ref "IC4") (pin "40") (pinfunction "PB4_40") (pintype "passive"))
    )
    (net (code "64") (name "unconnected-(IC4-PB5-Pad41)") (class "Default")
      (node (ref "IC4") (pin "41") (pinfunction "PB5_41") (pintype "passive"))
    )
    (net (code "65") (name "unconnected-(IC4-PB6-Pad42)") (class "Default")
      (node (ref "IC4") (pin "42") (pinfunction "PB6_42") (pintype "passive"))
    )
    (net (code "66") (name "unconnected-(IC4-PB8-Pad45)") (class "Default")
      (node (ref "IC4") (pin "45") (pinfunction "PB8_45") (pintype "passive"))
    )
    (net (code "67") (name "unconnected-(IC4-PB9-Pad46)") (class "Default")
      (node (ref "IC4") (pin "46") (pinfunction "PB9_46") (pintype "passive"))
    )
    (net (code "68") (name "unconnected-(IC4-PB12-Pad25)") (class "Default")
      (node (ref "IC4") (pin "25") (pinfunction "PB12_25") (pintype "passive"))
    )
    (net (code "69") (name "unconnected-(IC4-PB13-Pad26)") (class "Default")
      (node (ref "IC4") (pin "26") (pinfunction "PB13_26") (pintype "passive"))
    )
    (net (code "70") (name "unconnected-(IC4-PB14-Pad27)") (class "Default")
      (node (ref "IC4") (pin "27") (pinfunction "PB14_27") (pintype "passive"))
    )
    (net (code "71") (name "unconnected-(IC4-PB15-Pad28)") (class "Default")
      (node (ref "IC4") (pin "28") (pinfunction "PB15_28") (pintype "passive"))
    )
    (net (code "72") (name "unconnected-(IC4-PD0-OSC_IN-Pad5)") (class "Default")
      (node (ref "IC4") (pin "5") (pinfunction "PD0-OSC_IN_5") (pintype "passive"))
    )
    (net (code "73") (name "unconnected-(IC4-PD1-OSC_OUT-Pad6)") (class "Default")
      (node (ref "IC4") (pin "6") (pinfunction "PD1-OSC_OUT_6") (pintype "passive"))
    )
    (net (code "74") (name "unconnected-(IC5-NC-Pad2)") (class "Default")
      (node (ref "IC5") (pin "2") (pinfunction "NC_2") (pintype "passive"))
    )
    (net (code "75") (name "unconnected-(IC5-NC-Pad3)") (class "Default")
      (node (ref "IC5") (pin "3") (pinfunction "NC_3") (pintype "passive"))
    )
    (net (code "76") (name "unconnected-(IC5-NC-Pad4)") (class "Default")
      (node (ref "IC5") (pin "4") (pinfunction "NC_4") (pintype "passive"))
    )
    (net (code "77") (name "unconnected-(IC5-NC-Pad5)") (class "Default")
      (node (ref "IC5") (pin "5") (pinfunction "NC_5") (pintype "passive"))
    )
    (net (code "78") (name "unconnected-(IC5-NC-Pad14)") (class "Default")
      (node (ref "IC5") (pin "14") (pinfunction "NC_14") (pintype "passive"))
    )
    (net (code "79") (name "unconnected-(IC5-NC-Pad15)") (class "Default")
      (node (ref "IC5") (pin "15") (pinfunction "NC_15") (pintype "passive"))
    )
    (net (code "80") (name "unconnected-(IC5-NC-Pad16)") (class "Default")
      (node (ref "IC5") (pin "16") (pinfunction "NC_16") (pintype "passive"))
    )
    (net (code "81") (name "unconnected-(IC5-NC-Pad17)") (class "Default")
      (node (ref "IC5") (pin "17") (pinfunction "NC_17") (pintype "passive"))
    )
    (net (code "82") (name "unconnected-(IC5-RESV-Pad19)") (class "Default")
      (node (ref "IC5") (pin "19") (pinfunction "RESV_19") (pintype "passive"))
    )
    (net (code "83") (name "unconnected-(IC5-RESV-Pad21)") (class "Default")
      (node (ref "IC5") (pin "21") (pinfunction "RESV_21") (pintype "passive"))
    )
    (net (code "84") (name "unconnected-(IC5-RESV-Pad22)") (class "Default")
      (node (ref "IC5") (pin "22") (pinfunction "RESV_22") (pintype "passive"))
    )
    (net (code "85") (name "unconnected-(IC6-NC-Pad1)") (class "Default")
      (node (ref "IC6") (pin "1") (pinfunction "NC_1") (pintype "passive"))
    )
    (net (code "86") (name "unconnected-(IC6-NC-Pad4)") (class "Default")
      (node (ref "IC6") (pin "4") (pinfunction "NC_4") (pintype "passive"))
    )
    (net (code "87") (name "unconnected-(J1-D+-Pad3)") (class "Default")
      (node (ref "J1") (pin "3") (pinfunction "D+_3") (pintype "bidirectional"))
    )
    (net (code "88") (name "unconnected-(J1-D--Pad2)") (class "Default")
      (node (ref "J1") (pin "2") (pinfunction "D-_2") (pintype "bidirectional"))
    )
    (net (code "89") (name "unconnected-(J1-ID-Pad4)") (class "Default")
      (node (ref "J1") (pin "4") (pinfunction "ID_4") (pintype "passive"))
    )
  )
)
